# Projet_Elec_Groupe_8.net
KiCad netlist of a schematic drawn in EAGLE
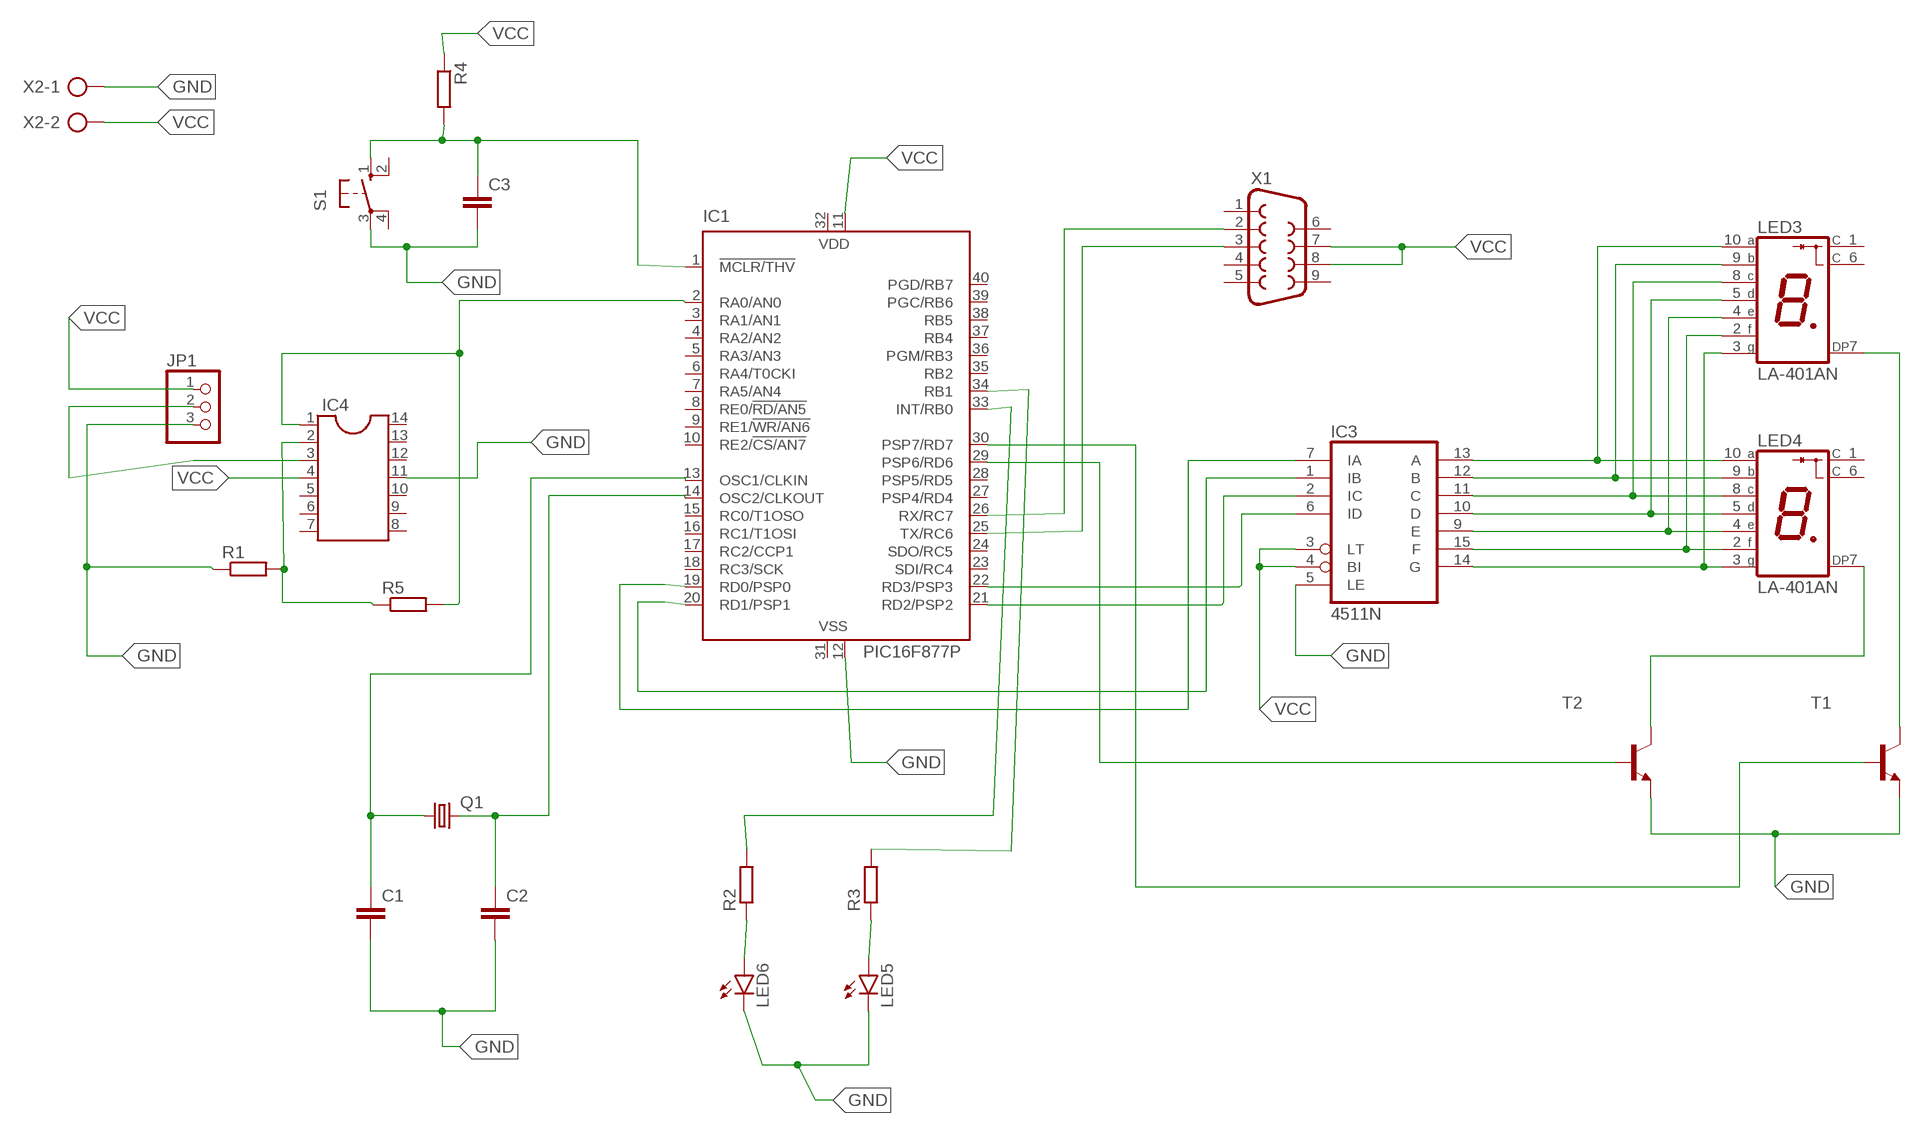
[diagram p0: schematic, sheet 1]

(export (version "E")
  (design (tool "Eeschema 10.0.6"))
  (components
    (comp (ref "C1")
      (value "C-EU025-025X050")
      (footprint "eagle-import:C025-025X050")
      (libsource (lib "eagle-import") (part "C-EU025-025X050"))
    )
    (comp (ref "C2")
      (value "C-EU025-025X050")
      (footprint "eagle-import:C025-025X050")
      (libsource (lib "eagle-import") (part "C-EU025-025X050"))
    )
    (comp (ref "C3")
      (value "C-EU025-025X050")
      (footprint "eagle-import:C025-025X050")
      (libsource (lib "eagle-import") (part "C-EU025-025X050"))
    )
    (comp (ref "IC1")
      (value "PIC16F877P")
      (footprint "eagle-import:DIL40")
      (fields (field (name "MF") "MICROCHIP") (field (name "MPN") "PIC16F877-04/P"))
      (libsource (lib "eagle-import") (part "PIC16F87P7"))
    )
    (comp (ref "IC3")
      (value "4511N")
      (footprint "eagle-import:DIL16")
      (libsource (lib "eagle-import") (part "4511N"))
    )
    (comp (ref "IC4")
      (value "DIL14")
      (footprint "eagle-import:DIL14")
      (libsource (lib "eagle-import") (part "DIL14"))
    )
    (comp (ref "JP1")
      (value "PINHD-1X3")
      (footprint "eagle-import:1X03")
      (libsource (lib "eagle-import") (part "PINHD-1X3"))
    )
    (comp (ref "LED3")
      (value "LA-401AN")
      (footprint "eagle-import:LA-401")
      (libsource (lib "eagle-import") (part "LA-401NA"))
    )
    (comp (ref "LED4")
      (value "LA-401AN")
      (footprint "eagle-import:LA-401")
      (libsource (lib "eagle-import") (part "LA-401NA"))
    )
    (comp (ref "LED5")
      (value "LEDLD260")
      (footprint "eagle-import:LD260")
      (libsource (lib "eagle-import") (part "LEDLD260"))
    )
    (comp (ref "LED6")
      (value "LEDLD260")
      (footprint "eagle-import:LD260")
      (libsource (lib "eagle-import") (part "LEDLD260"))
    )
    (comp (ref "Q1")
      (value "CRYSTALHC18U-V")
      (footprint "eagle-import:HC18U-V")
      (libsource (lib "eagle-import") (part "CRYSTALHC18U-V"))
    )
    (comp (ref "R1")
      (value "R-EU_0204/5")
      (footprint "eagle-import:0204_5")
      (libsource (lib "eagle-import") (part "R-EU_0204/5"))
    )
    (comp (ref "R2")
      (value "R-EU_0204/5")
      (footprint "eagle-import:0204_5")
      (libsource (lib "eagle-import") (part "R-EU_0204/5"))
    )
    (comp (ref "R3")
      (value "R-EU_0204/5")
      (footprint "eagle-import:0204_5")
      (libsource (lib "eagle-import") (part "R-EU_0204/5"))
    )
    (comp (ref "R4")
      (value "R-EU_0204/5")
      (footprint "eagle-import:0204_5")
      (libsource (lib "eagle-import") (part "R-EU_0204/5"))
    )
    (comp (ref "R5")
      (value "R-EU_0204/5")
      (footprint "eagle-import:0204_5")
      (libsource (lib "eagle-import") (part "R-EU_0204/5"))
    )
    (comp (ref "S1")
      (value "10-XX")
      (footprint "eagle-import:B3F-10XX")
      (fields (field (name "MPN") "B3F-1000"))
      (libsource (lib "eagle-import") (part "10-XX"))
    )
    (comp (ref "T1")
      (value "-NPN-TO92-EBC")
      (footprint "eagle-import:TO92-EBC")
      (libsource (lib "eagle-import") (part "-NPN-TO92-EBC"))
    )
    (comp (ref "T2")
      (value "-NPN-TO92-EBC")
      (footprint "eagle-import:TO92-EBC")
      (libsource (lib "eagle-import") (part "-NPN-TO92-EBC"))
    )
    (comp (ref "X1")
      (value "F09V")
      (footprint "eagle-import:F09V")
      (libsource (lib "eagle-import") (part "F09V"))
    )
    (comp (ref "X2")
      (value "AK300/2")
      (footprint "eagle-import:AK300_2")
      (libsource (lib "eagle-import") (part "AK300/2"))
    )
  )
  (nets
    (net (code "1") (name "/VDD") (class "Default")
      (node (ref "IC1") (pin "32") (pinfunction "VDD_32") (pintype "power_in"))
    )
    (net (code "2") (name "/VSS") (class "Default")
      (node (ref "IC1") (pin "31") (pinfunction "VSS_31") (pintype "power_in"))
    )
    (net (code "3") (name "GND") (class "Default")
      (node (ref "C1") (pin "2") (pinfunction "2_2") (pintype "passive"))
      (node (ref "C2") (pin "2") (pinfunction "2_2") (pintype "passive"))
      (node (ref "C3") (pin "2") (pinfunction "2_2") (pintype "passive"))
      (node (ref "IC1") (pin "12") (pinfunction "VSS_12") (pintype "power_in"))
      (node (ref "IC3") (pin "5") (pinfunction "LE_5") (pintype "input"))
      (node (ref "IC4") (pin "11") (pinfunction "11_11") (pintype "passive"))
      (node (ref "JP1") (pin "3") (pinfunction "3_3") (pintype "passive"))
      (node (ref "LED5") (pin "K") (pinfunction "C_K") (pintype "passive"))
      (node (ref "LED6") (pin "K") (pinfunction "C_K") (pintype "passive"))
      (node (ref "R1") (pin "1") (pinfunction "1_1") (pintype "passive"))
      (node (ref "S1") (pin "3") (pinfunction "P_3") (pintype "passive"))
      (node (ref "T1") (pin "E") (pinfunction "E_E") (pintype "passive"))
      (node (ref "T2") (pin "E") (pinfunction "E_E") (pintype "passive"))
      (node (ref "X2") (pin "1") (pinfunction "KL_1") (pintype "passive"))
    )
    (net (code "4") (name "Net-(IC1-INT{slash}RB0)") (class "Default")
      (node (ref "IC1") (pin "33") (pinfunction "INT/RB0_33") (pintype "bidirectional"))
      (node (ref "R2") (pin "2") (pinfunction "2_2") (pintype "passive"))
    )
    (net (code "5") (name "Net-(IC1-OSC1{slash}CLKIN)") (class "Default")
      (node (ref "C1") (pin "1") (pinfunction "1_1") (pintype "passive"))
      (node (ref "IC1") (pin "13") (pinfunction "OSC1/CLKIN_13") (pintype "input"))
      (node (ref "Q1") (pin "1") (pinfunction "1_1") (pintype "passive"))
    )
    (net (code "6") (name "Net-(IC1-OSC2{slash}CLKOUT)") (class "Default")
      (node (ref "C2") (pin "1") (pinfunction "1_1") (pintype "passive"))
      (node (ref "IC1") (pin "14") (pinfunction "OSC2/CLKOUT_14") (pintype "output"))
      (node (ref "Q1") (pin "2") (pinfunction "2_2") (pintype "passive"))
    )
    (net (code "7") (name "Net-(IC1-PSP6{slash}RD6)") (class "Default")
      (node (ref "IC1") (pin "29") (pinfunction "PSP6/RD6_29") (pintype "bidirectional"))
      (node (ref "T2") (pin "B") (pinfunction "B_B") (pintype "passive"))
    )
    (net (code "8") (name "Net-(IC1-PSP7{slash}RD7)") (class "Default")
      (node (ref "IC1") (pin "30") (pinfunction "PSP7/RD7_30") (pintype "bidirectional"))
      (node (ref "T1") (pin "B") (pinfunction "B_B") (pintype "passive"))
    )
    (net (code "9") (name "Net-(IC1-RA0{slash}AN0)") (class "Default")
      (node (ref "IC1") (pin "2") (pinfunction "RA0/AN0_2") (pintype "bidirectional"))
      (node (ref "IC4") (pin "1") (pinfunction "1_1") (pintype "passive"))
      (node (ref "R5") (pin "2") (pinfunction "2_2") (pintype "passive"))
    )
    (net (code "10") (name "Net-(IC1-RB1)") (class "Default")
      (node (ref "IC1") (pin "34") (pinfunction "RB1_34") (pintype "bidirectional"))
      (node (ref "R3") (pin "2") (pinfunction "2_2") (pintype "passive"))
    )
    (net (code "11") (name "Net-(IC1-RD0{slash}PSP0)") (class "Default")
      (node (ref "IC1") (pin "19") (pinfunction "RD0/PSP0_19") (pintype "bidirectional"))
      (node (ref "IC3") (pin "7") (pinfunction "IA_7") (pintype "input"))
    )
    (net (code "12") (name "Net-(IC1-RD1{slash}PSP1)") (class "Default")
      (node (ref "IC1") (pin "20") (pinfunction "RD1/PSP1_20") (pintype "bidirectional"))
      (node (ref "IC3") (pin "1") (pinfunction "IB_1") (pintype "input"))
    )
    (net (code "13") (name "Net-(IC1-RD2{slash}PSP2)") (class "Default")
      (node (ref "IC1") (pin "21") (pinfunction "RD2/PSP2_21") (pintype "bidirectional"))
      (node (ref "IC3") (pin "2") (pinfunction "IC_2") (pintype "input"))
    )
    (net (code "14") (name "Net-(IC1-RD3{slash}PSP3)") (class "Default")
      (node (ref "IC1") (pin "22") (pinfunction "RD3/PSP3_22") (pintype "bidirectional"))
      (node (ref "IC3") (pin "6") (pinfunction "ID_6") (pintype "input"))
    )
    (net (code "15") (name "Net-(IC1-RX{slash}RC7)") (class "Default")
      (node (ref "IC1") (pin "26") (pinfunction "RX/RC7_26") (pintype "bidirectional"))
      (node (ref "X1") (pin "2") (pinfunction "2_2") (pintype "passive"))
    )
    (net (code "16") (name "Net-(IC1-TX{slash}RC6)") (class "Default")
      (node (ref "IC1") (pin "25") (pinfunction "TX/RC6_25") (pintype "bidirectional"))
      (node (ref "X1") (pin "3") (pinfunction "3_3") (pintype "passive"))
    )
    (net (code "17") (name "Net-(IC1-~{MCLR{slash}THV})") (class "Default")
      (node (ref "C3") (pin "1") (pinfunction "1_1") (pintype "passive"))
      (node (ref "IC1") (pin "1") (pinfunction "~{MCLR/THV}_1") (pintype "input"))
      (node (ref "R4") (pin "2") (pinfunction "2_2") (pintype "passive"))
      (node (ref "S1") (pin "1") (pinfunction "S_1") (pintype "passive"))
    )
    (net (code "18") (name "Net-(IC3A-A)") (class "Default")
      (node (ref "IC3") (pin "13") (pinfunction "A_13") (pintype "output"))
      (node (ref "LED3") (pin "10") (pinfunction "A_10") (pintype "passive"))
      (node (ref "LED4") (pin "10") (pinfunction "A_10") (pintype "passive"))
    )
    (net (code "19") (name "Net-(IC3A-B)") (class "Default")
      (node (ref "IC3") (pin "12") (pinfunction "B_12") (pintype "output"))
      (node (ref "LED3") (pin "9") (pinfunction "B_9") (pintype "passive"))
      (node (ref "LED4") (pin "9") (pinfunction "B_9") (pintype "passive"))
    )
    (net (code "20") (name "Net-(IC3A-C)") (class "Default")
      (node (ref "IC3") (pin "11") (pinfunction "C_11") (pintype "output"))
      (node (ref "LED3") (pin "8") (pinfunction "C_8") (pintype "passive"))
      (node (ref "LED4") (pin "8") (pinfunction "C_8") (pintype "passive"))
    )
    (net (code "21") (name "Net-(IC3A-D)") (class "Default")
      (node (ref "IC3") (pin "10") (pinfunction "D_10") (pintype "output"))
      (node (ref "LED3") (pin "5") (pinfunction "D_5") (pintype "passive"))
      (node (ref "LED4") (pin "5") (pinfunction "D_5") (pintype "passive"))
    )
    (net (code "22") (name "Net-(IC3A-E)") (class "Default")
      (node (ref "IC3") (pin "9") (pinfunction "E_9") (pintype "output"))
      (node (ref "LED3") (pin "4") (pinfunction "E_4") (pintype "passive"))
      (node (ref "LED4") (pin "4") (pinfunction "E_4") (pintype "passive"))
    )
    (net (code "23") (name "Net-(IC3A-F)") (class "Default")
      (node (ref "IC3") (pin "15") (pinfunction "F_15") (pintype "output"))
      (node (ref "LED3") (pin "2") (pinfunction "F_2") (pintype "passive"))
      (node (ref "LED4") (pin "2") (pinfunction "F_2") (pintype "passive"))
    )
    (net (code "24") (name "Net-(IC3A-G)") (class "Default")
      (node (ref "IC3") (pin "14") (pinfunction "G_14") (pintype "output"))
      (node (ref "LED3") (pin "3") (pinfunction "G_3") (pintype "passive"))
      (node (ref "LED4") (pin "3") (pinfunction "G_3") (pintype "passive"))
    )
    (net (code "25") (name "Net-(IC4-Pad2)") (class "Default")
      (node (ref "IC4") (pin "2") (pinfunction "2_2") (pintype "passive"))
      (node (ref "R1") (pin "2") (pinfunction "2_2") (pintype "passive"))
      (node (ref "R5") (pin "1") (pinfunction "1_1") (pintype "passive"))
    )
    (net (code "26") (name "Net-(IC4-Pad3)") (class "Default")
      (node (ref "IC4") (pin "3") (pinfunction "3_3") (pintype "passive"))
      (node (ref "JP1") (pin "2") (pinfunction "2_2") (pintype "passive"))
    )
    (net (code "27") (name "Net-(LED3-DP)") (class "Default")
      (node (ref "LED3") (pin "7") (pinfunction "DP_7") (pintype "passive"))
      (node (ref "T1") (pin "C") (pinfunction "C_C") (pintype "passive"))
    )
    (net (code "28") (name "Net-(LED4-DP)") (class "Default")
      (node (ref "LED4") (pin "7") (pinfunction "DP_7") (pintype "passive"))
      (node (ref "T2") (pin "C") (pinfunction "C_C") (pintype "passive"))
    )
    (net (code "29") (name "Net-(LED5-PadA)") (class "Default")
      (node (ref "LED5") (pin "A") (pinfunction "A_A") (pintype "passive"))
      (node (ref "R3") (pin "1") (pinfunction "1_1") (pintype "passive"))
    )
    (net (code "30") (name "Net-(LED6-PadA)") (class "Default")
      (node (ref "LED6") (pin "A") (pinfunction "A_A") (pintype "passive"))
      (node (ref "R2") (pin "1") (pinfunction "1_1") (pintype "passive"))
    )
    (net (code "31") (name "VCC") (class "Default")
      (node (ref "IC1") (pin "11") (pinfunction "VDD_11") (pintype "power_in"))
      (node (ref "IC3") (pin "3") (pinfunction "LT_3") (pintype "input"))
      (node (ref "IC3") (pin "4") (pinfunction "BI_4") (pintype "input"))
      (node (ref "IC4") (pin "4") (pinfunction "4_4") (pintype "passive"))
      (node (ref "JP1") (pin "1") (pinfunction "1_1") (pintype "passive"))
      (node (ref "R4") (pin "1") (pinfunction "1_1") (pintype "passive"))
      (node (ref "X1") (pin "7") (pinfunction "7_7") (pintype "passive"))
      (node (ref "X1") (pin "8") (pinfunction "8_8") (pintype "passive"))
      (node (ref "X2") (pin "2") (pinfunction "KL_2") (pintype "passive"))
    )
    (net (code "32") (name "unconnected-(IC1-PGC{slash}RB6-Pad39)") (class "Default")
      (node (ref "IC1") (pin "39") (pinfunction "PGC/RB6_39") (pintype "bidirectional"))
    )
    (net (code "33") (name "unconnected-(IC1-PGD{slash}RB7-Pad40)") (class "Default")
      (node (ref "IC1") (pin "40") (pinfunction "PGD/RB7_40") (pintype "bidirectional"))
    )
    (net (code "34") (name "unconnected-(IC1-PGM{slash}RB3-Pad36)") (class "Default")
      (node (ref "IC1") (pin "36") (pinfunction "PGM/RB3_36") (pintype "bidirectional"))
    )
    (net (code "35") (name "unconnected-(IC1-PSP4{slash}RD4-Pad27)") (class "Default")
      (node (ref "IC1") (pin "27") (pinfunction "PSP4/RD4_27") (pintype "bidirectional"))
    )
    (net (code "36") (name "unconnected-(IC1-PSP5{slash}RD5-Pad28)") (class "Default")
      (node (ref "IC1") (pin "28") (pinfunction "PSP5/RD5_28") (pintype "bidirectional"))
    )
    (net (code "37") (name "unconnected-(IC1-RA1{slash}AN1-Pad3)") (class "Default")
      (node (ref "IC1") (pin "3") (pinfunction "RA1/AN1_3") (pintype "bidirectional"))
    )
    (net (code "38") (name "unconnected-(IC1-RA2{slash}AN2-Pad4)") (class "Default")
      (node (ref "IC1") (pin "4") (pinfunction "RA2/AN2_4") (pintype "bidirectional"))
    )
    (net (code "39") (name "unconnected-(IC1-RA3{slash}AN3-Pad5)") (class "Default")
      (node (ref "IC1") (pin "5") (pinfunction "RA3/AN3_5") (pintype "bidirectional"))
    )
    (net (code "40") (name "unconnected-(IC1-RA4{slash}T0CKI-Pad6)") (class "Default")
      (node (ref "IC1") (pin "6") (pinfunction "RA4/T0CKI_6") (pintype "bidirectional"))
    )
    (net (code "41") (name "unconnected-(IC1-RA5{slash}AN4-Pad7)") (class "Default")
      (node (ref "IC1") (pin "7") (pinfunction "RA5/AN4_7") (pintype "bidirectional"))
    )
    (net (code "42") (name "unconnected-(IC1-RB2-Pad35)") (class "Default")
      (node (ref "IC1") (pin "35") (pinfunction "RB2_35") (pintype "bidirectional"))
    )
    (net (code "43") (name "unconnected-(IC1-RB4-Pad37)") (class "Default")
      (node (ref "IC1") (pin "37") (pinfunction "RB4_37") (pintype "bidirectional"))
    )
    (net (code "44") (name "unconnected-(IC1-RB5-Pad38)") (class "Default")
      (node (ref "IC1") (pin "38") (pinfunction "RB5_38") (pintype "bidirectional"))
    )
    (net (code "45") (name "unconnected-(IC1-RC0{slash}T1OSO-Pad15)") (class "Default")
      (node (ref "IC1") (pin "15") (pinfunction "RC0/T1OSO_15") (pintype "bidirectional"))
    )
    (net (code "46") (name "unconnected-(IC1-RC1{slash}T1OSI-Pad16)") (class "Default")
      (node (ref "IC1") (pin "16") (pinfunction "RC1/T1OSI_16") (pintype "bidirectional"))
    )
    (net (code "47") (name "unconnected-(IC1-RC2{slash}CCP1-Pad17)") (class "Default")
      (node (ref "IC1") (pin "17") (pinfunction "RC2/CCP1_17") (pintype "bidirectional"))
    )
    (net (code "48") (name "unconnected-(IC1-RC3{slash}SCK-Pad18)") (class "Default")
      (node (ref "IC1") (pin "18") (pinfunction "RC3/SCK_18") (pintype "bidirectional"))
    )
    (net (code "49") (name "unconnected-(IC1-RE0{slash}~{RD{slash}AN5}-Pad8)") (class "Default")
      (node (ref "IC1") (pin "8") (pinfunction "RE0/~{RD/AN5}_8") (pintype "bidirectional"))
    )
    (net (code "50") (name "unconnected-(IC1-RE1{slash}~{WR{slash}AN6}-Pad9)") (class "Default")
      (node (ref "IC1") (pin "9") (pinfunction "RE1/~{WR/AN6}_9") (pintype "bidirectional"))
    )
    (net (code "51") (name "unconnected-(IC1-RE2{slash}~{CS{slash}AN7}-Pad10)") (class "Default")
      (node (ref "IC1") (pin "10") (pinfunction "RE2/~{CS/AN7}_10") (pintype "bidirectional"))
    )
    (net (code "52") (name "unconnected-(IC1-SDI{slash}RC4-Pad23)") (class "Default")
      (node (ref "IC1") (pin "23") (pinfunction "SDI/RC4_23") (pintype "bidirectional"))
    )
    (net (code "53") (name "unconnected-(IC1-SDO{slash}RC5-Pad24)") (class "Default")
      (node (ref "IC1") (pin "24") (pinfunction "SDO/RC5_24") (pintype "bidirectional"))
    )
    (net (code "54") (name "unconnected-(IC4-Pad5)") (class "Default")
      (node (ref "IC4") (pin "5") (pinfunction "5_5") (pintype "passive"))
    )
    (net (code "55") (name "unconnected-(IC4-Pad6)") (class "Default")
      (node (ref "IC4") (pin "6") (pinfunction "6_6") (pintype "passive"))
    )
    (net (code "56") (name "unconnected-(IC4-Pad7)") (class "Default")
      (node (ref "IC4") (pin "7") (pinfunction "7_7") (pintype "passive"))
    )
    (net (code "57") (name "unconnected-(IC4-Pad8)") (class "Default")
      (node (ref "IC4") (pin "8") (pinfunction "8_8") (pintype "passive"))
    )
    (net (code "58") (name "unconnected-(IC4-Pad9)") (class "Default")
      (node (ref "IC4") (pin "9") (pinfunction "9_9") (pintype "passive"))
    )
    (net (code "59") (name "unconnected-(IC4-Pad10)") (class "Default")
      (node (ref "IC4") (pin "10") (pinfunction "10_10") (pintype "passive"))
    )
    (net (code "60") (name "unconnected-(IC4-Pad12)") (class "Default")
      (node (ref "IC4") (pin "12") (pinfunction "12_12") (pintype "passive"))
    )
    (net (code "61") (name "unconnected-(IC4-Pad13)") (class "Default")
      (node (ref "IC4") (pin "13") (pinfunction "13_13") (pintype "passive"))
    )
    (net (code "62") (name "unconnected-(IC4-Pad14)") (class "Default")
      (node (ref "IC4") (pin "14") (pinfunction "14_14") (pintype "passive"))
    )
    (net (code "63") (name "unconnected-(LED3-C-Pad1)") (class "Default")
      (node (ref "LED3") (pin "1") (pinfunction "C_1") (pintype "passive"))
    )
    (net (code "64") (name "unconnected-(LED3-C-Pad6)") (class "Default")
      (node (ref "LED3") (pin "6") (pinfunction "C_6") (pintype "passive"))
    )
    (net (code "65") (name "unconnected-(LED4-C-Pad1)") (class "Default")
      (node (ref "LED4") (pin "1") (pinfunction "C_1") (pintype "passive"))
    )
    (net (code "66") (name "unconnected-(LED4-C-Pad6)") (class "Default")
      (node (ref "LED4") (pin "6") (pinfunction "C_6") (pintype "passive"))
    )
    (net (code "67") (name "unconnected-(S1-P1-Pad4)") (class "Default")
      (node (ref "S1") (pin "4") (pinfunction "P1_4") (pintype "passive"))
    )
    (net (code "68") (name "unconnected-(S1-S1-Pad2)") (class "Default")
      (node (ref "S1") (pin "2") (pinfunction "S1_2") (pintype "passive"))
    )
    (net (code "69") (name "unconnected-(X1-Pad1)") (class "Default")
      (node (ref "X1") (pin "1") (pinfunction "1_1") (pintype "passive"))
    )
    (net (code "70") (name "unconnected-(X1-Pad4)") (class "Default")
      (node (ref "X1") (pin "4") (pinfunction "4_4") (pintype "passive"))
    )
    (net (code "71") (name "unconnected-(X1-Pad5)") (class "Default")
      (node (ref "X1") (pin "5") (pinfunction "5_5") (pintype "passive"))
    )
    (net (code "72") (name "unconnected-(X1-Pad6)") (class "Default")
      (node (ref "X1") (pin "6") (pinfunction "6_6") (pintype "passive"))
    )
    (net (code "73") (name "unconnected-(X1-Pad9)") (class "Default")
      (node (ref "X1") (pin "9") (pinfunction "9_9") (pintype "passive"))
    )
  )
)
